# Busboard_v12.net
KiCad netlist of a schematic drawn in EAGLE
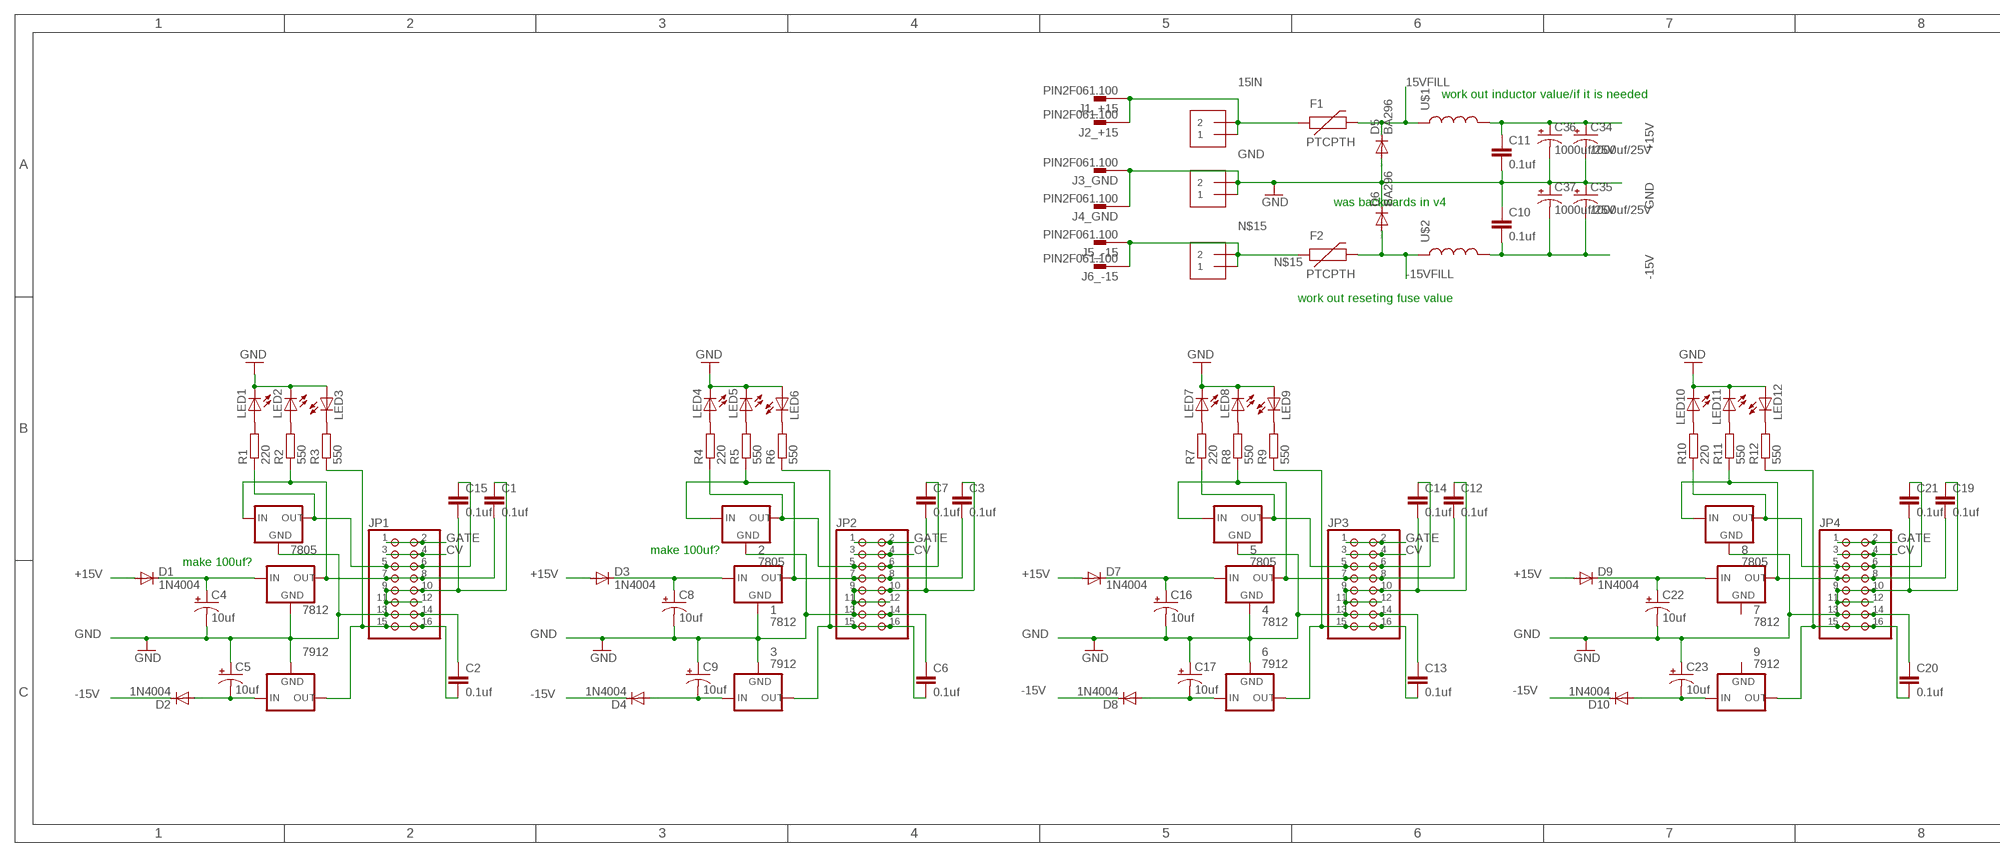
[diagram p0: schematic, sheet 1, part 1 of 2]
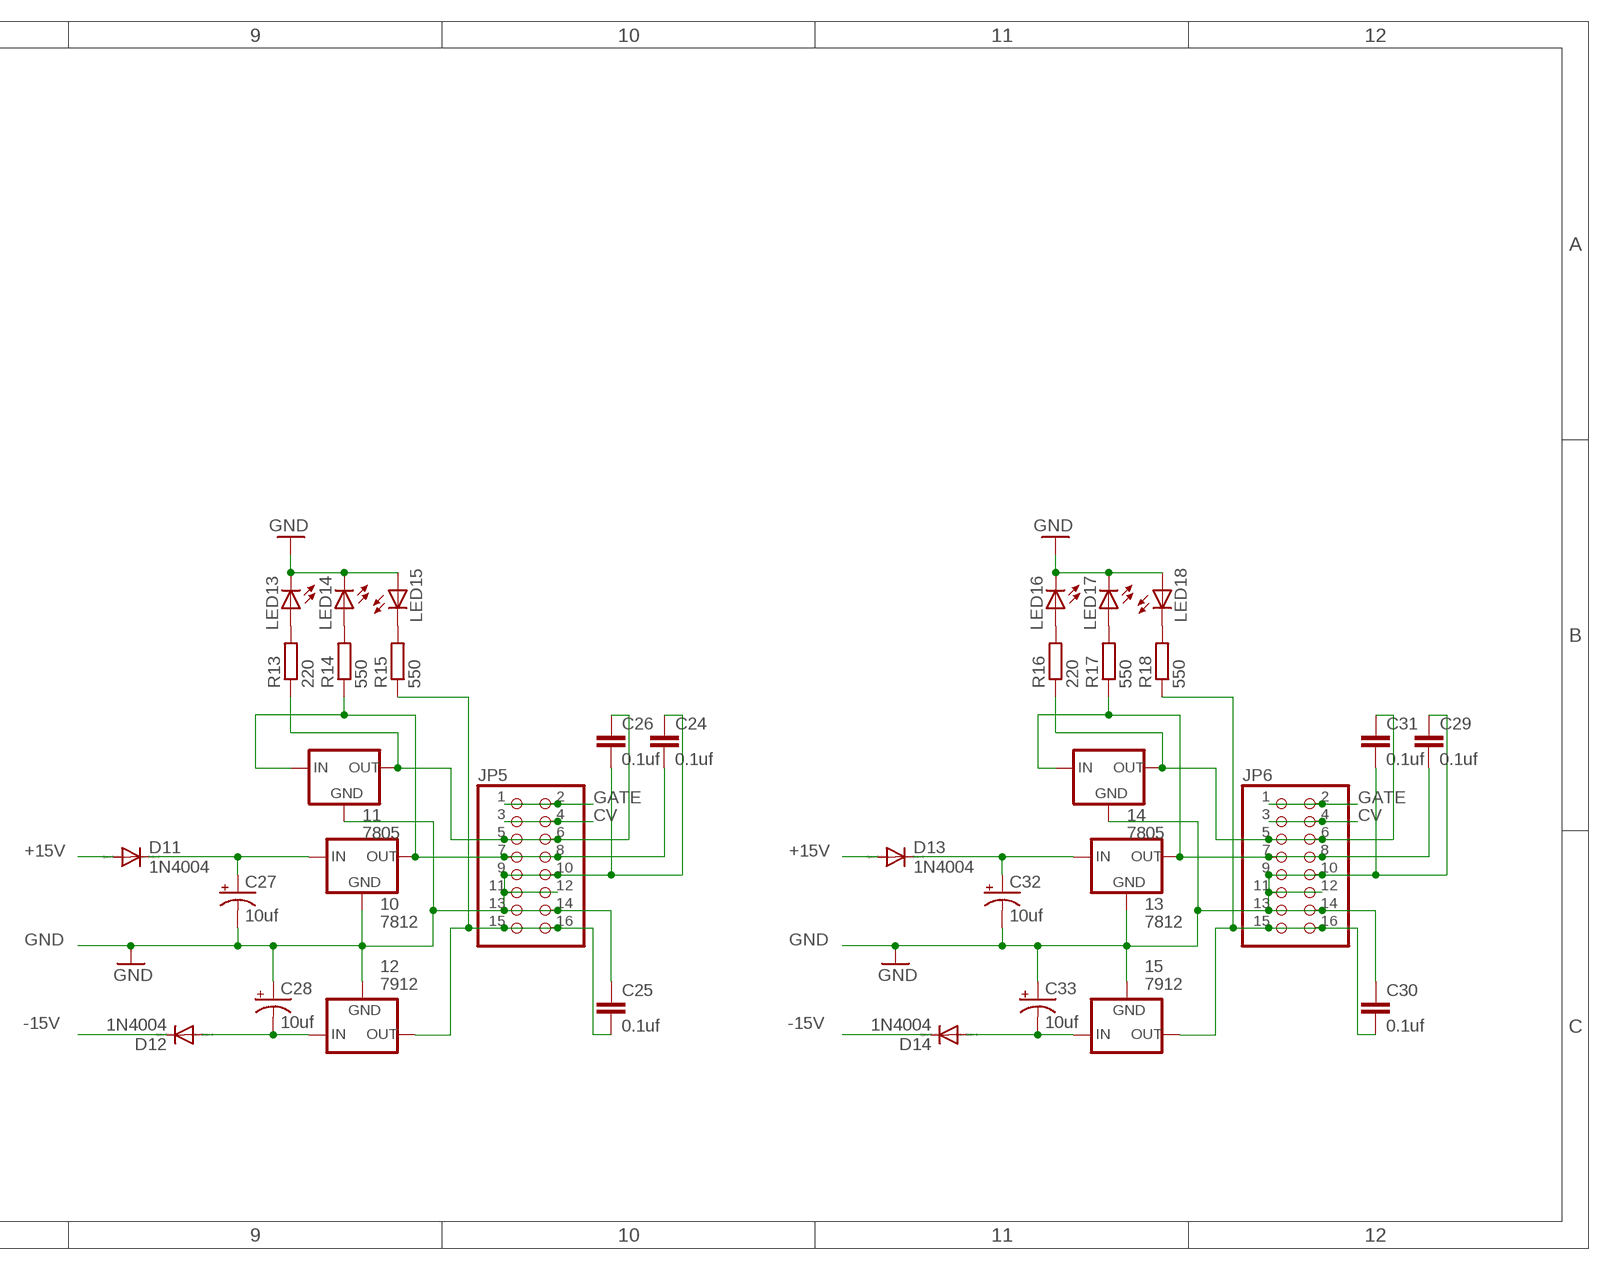
[diagram p1: schematic, sheet 1, part 2 of 2]

(export (version "E")
  (design (tool "Eeschema 10.0.6"))
  (components
    (comp (ref "+15V")
      (value "1X2-3.5MM")
      (footprint "eagle-import:1X2-3.5MM")
      (libsource (lib "eagle-import") (part "1X2-3.5MM"))
    )
    (comp (ref "-15V")
      (value "1X2-3.5MM")
      (footprint "eagle-import:1X2-3.5MM")
      (libsource (lib "eagle-import") (part "1X2-3.5MM"))
    )
    (comp (ref "1")
      (value "7812")
      (footprint "eagle-import:78MXXS")
      (libsource (lib "eagle-import") (part "78MXXS"))
    )
    (comp (ref "2")
      (value "7805")
      (footprint "eagle-import:78MXXS")
      (libsource (lib "eagle-import") (part "78MXXS"))
    )
    (comp (ref "3")
      (value "7912")
      (footprint "eagle-import:79XXS")
      (libsource (lib "eagle-import") (part "79XXS"))
    )
    (comp (ref "4")
      (value "7812")
      (footprint "eagle-import:78MXXS")
      (libsource (lib "eagle-import") (part "78MXXS"))
    )
    (comp (ref "5")
      (value "7805")
      (footprint "eagle-import:78MXXS")
      (libsource (lib "eagle-import") (part "78MXXS"))
    )
    (comp (ref "6")
      (value "7912")
      (footprint "eagle-import:79XXS")
      (libsource (lib "eagle-import") (part "79XXS"))
    )
    (comp (ref "7")
      (value "7812")
      (footprint "eagle-import:78MXXS")
      (libsource (lib "eagle-import") (part "78MXXS"))
    )
    (comp (ref "8")
      (value "7805")
      (footprint "eagle-import:78MXXS")
      (libsource (lib "eagle-import") (part "78MXXS"))
    )
    (comp (ref "9")
      (value "7912")
      (footprint "eagle-import:79XXS")
      (libsource (lib "eagle-import") (part "79XXS"))
    )
    (comp (ref "10")
      (value "7812")
      (footprint "eagle-import:78MXXS")
      (libsource (lib "eagle-import") (part "78MXXS"))
    )
    (comp (ref "11")
      (value "7805")
      (footprint "eagle-import:78MXXS")
      (libsource (lib "eagle-import") (part "78MXXS"))
    )
    (comp (ref "12")
      (value "7912")
      (footprint "eagle-import:79XXS")
      (libsource (lib "eagle-import") (part "79XXS"))
    )
    (comp (ref "13")
      (value "7812")
      (footprint "eagle-import:78MXXS")
      (libsource (lib "eagle-import") (part "78MXXS"))
    )
    (comp (ref "14")
      (value "7805")
      (footprint "eagle-import:78MXXS")
      (libsource (lib "eagle-import") (part "78MXXS"))
    )
    (comp (ref "15")
      (value "7912")
      (footprint "eagle-import:79XXS")
      (libsource (lib "eagle-import") (part "79XXS"))
    )
    (comp (ref "7805")
      (value "78MXXS")
      (footprint "eagle-import:78MXXS")
      (libsource (lib "eagle-import") (part "78MXXS"))
    )
    (comp (ref "7812")
      (value "78MXXS")
      (footprint "eagle-import:78MXXS")
      (libsource (lib "eagle-import") (part "78MXXS"))
    )
    (comp (ref "7912")
      (value "79XXS")
      (footprint "eagle-import:79XXS")
      (libsource (lib "eagle-import") (part "79XXS"))
    )
    (comp (ref "C1")
      (value "0.1uf")
      (footprint "eagle-import:CAP-PTH-SMALL-KIT")
      (libsource (lib "eagle-import") (part "0.1UF-50V-20%(PTH)KIT-EZ"))
    )
    (comp (ref "C2")
      (value "0.1uf")
      (footprint "eagle-import:CAP-PTH-SMALL-KIT")
      (libsource (lib "eagle-import") (part "0.1UF-50V-20%(PTH)KIT-EZ"))
    )
    (comp (ref "C3")
      (value "0.1uf")
      (footprint "eagle-import:CAP-PTH-SMALL-KIT")
      (libsource (lib "eagle-import") (part "0.1UF-50V-20%(PTH)KIT-EZ"))
    )
    (comp (ref "C4")
      (value "10uf")
      (footprint "eagle-import:CPOL-RADIAL-10UF-25V")
      (libsource (lib "eagle-import") (part "10UF-25V-20%(PTH)"))
    )
    (comp (ref "C5")
      (value "10uf")
      (footprint "eagle-import:CPOL-RADIAL-10UF-25V")
      (libsource (lib "eagle-import") (part "10UF-25V-20%(PTH)"))
    )
    (comp (ref "C6")
      (value "0.1uf")
      (footprint "eagle-import:CAP-PTH-SMALL-KIT")
      (libsource (lib "eagle-import") (part "0.1UF-50V-20%(PTH)KIT-EZ"))
    )
    (comp (ref "C7")
      (value "0.1uf")
      (footprint "eagle-import:CAP-PTH-SMALL-KIT")
      (libsource (lib "eagle-import") (part "0.1UF-50V-20%(PTH)KIT-EZ"))
    )
    (comp (ref "C8")
      (value "10uf")
      (footprint "eagle-import:CPOL-RADIAL-10UF-25V")
      (libsource (lib "eagle-import") (part "10UF-25V-20%(PTH)"))
    )
    (comp (ref "C9")
      (value "10uf")
      (footprint "eagle-import:CPOL-RADIAL-10UF-25V")
      (libsource (lib "eagle-import") (part "10UF-25V-20%(PTH)"))
    )
    (comp (ref "C10")
      (value "0.1uf")
      (footprint "eagle-import:CAP-PTH-SMALL-KIT")
      (libsource (lib "eagle-import") (part "0.1UF-50V-20%(PTH)KIT-EZ"))
    )
    (comp (ref "C11")
      (value "0.1uf")
      (footprint "eagle-import:CAP-PTH-SMALL-KIT")
      (libsource (lib "eagle-import") (part "0.1UF-50V-20%(PTH)KIT-EZ"))
    )
    (comp (ref "C12")
      (value "0.1uf")
      (footprint "eagle-import:CAP-PTH-SMALL-KIT")
      (libsource (lib "eagle-import") (part "0.1UF-50V-20%(PTH)KIT-EZ"))
    )
    (comp (ref "C13")
      (value "0.1uf")
      (footprint "eagle-import:CAP-PTH-SMALL-KIT")
      (libsource (lib "eagle-import") (part "0.1UF-50V-20%(PTH)KIT-EZ"))
    )
    (comp (ref "C14")
      (value "0.1uf")
      (footprint "eagle-import:CAP-PTH-SMALL-KIT")
      (libsource (lib "eagle-import") (part "0.1UF-50V-20%(PTH)KIT-EZ"))
    )
    (comp (ref "C15")
      (value "0.1uf")
      (footprint "eagle-import:CAP-PTH-SMALL-KIT")
      (libsource (lib "eagle-import") (part "0.1UF-50V-20%(PTH)KIT-EZ"))
    )
    (comp (ref "C16")
      (value "10uf")
      (footprint "eagle-import:CPOL-RADIAL-10UF-25V")
      (libsource (lib "eagle-import") (part "10UF-25V-20%(PTH)"))
    )
    (comp (ref "C17")
      (value "10uf")
      (footprint "eagle-import:CPOL-RADIAL-10UF-25V")
      (libsource (lib "eagle-import") (part "10UF-25V-20%(PTH)"))
    )
    (comp (ref "C19")
      (value "0.1uf")
      (footprint "eagle-import:CAP-PTH-SMALL-KIT")
      (libsource (lib "eagle-import") (part "0.1UF-50V-20%(PTH)KIT-EZ"))
    )
    (comp (ref "C20")
      (value "0.1uf")
      (footprint "eagle-import:CAP-PTH-SMALL-KIT")
      (libsource (lib "eagle-import") (part "0.1UF-50V-20%(PTH)KIT-EZ"))
    )
    (comp (ref "C21")
      (value "0.1uf")
      (footprint "eagle-import:CAP-PTH-SMALL-KIT")
      (libsource (lib "eagle-import") (part "0.1UF-50V-20%(PTH)KIT-EZ"))
    )
    (comp (ref "C22")
      (value "10uf")
      (footprint "eagle-import:CPOL-RADIAL-10UF-25V")
      (libsource (lib "eagle-import") (part "10UF-25V-20%(PTH)"))
    )
    (comp (ref "C23")
      (value "10uf")
      (footprint "eagle-import:CPOL-RADIAL-10UF-25V")
      (libsource (lib "eagle-import") (part "10UF-25V-20%(PTH)"))
    )
    (comp (ref "C24")
      (value "0.1uf")
      (footprint "eagle-import:CAP-PTH-SMALL-KIT")
      (libsource (lib "eagle-import") (part "0.1UF-50V-20%(PTH)KIT-EZ"))
    )
    (comp (ref "C25")
      (value "0.1uf")
      (footprint "eagle-import:CAP-PTH-SMALL-KIT")
      (libsource (lib "eagle-import") (part "0.1UF-50V-20%(PTH)KIT-EZ"))
    )
    (comp (ref "C26")
      (value "0.1uf")
      (footprint "eagle-import:CAP-PTH-SMALL-KIT")
      (libsource (lib "eagle-import") (part "0.1UF-50V-20%(PTH)KIT-EZ"))
    )
    (comp (ref "C27")
      (value "10uf")
      (footprint "eagle-import:CPOL-RADIAL-10UF-25V")
      (libsource (lib "eagle-import") (part "10UF-25V-20%(PTH)"))
    )
    (comp (ref "C28")
      (value "10uf")
      (footprint "eagle-import:CPOL-RADIAL-10UF-25V")
      (libsource (lib "eagle-import") (part "10UF-25V-20%(PTH)"))
    )
    (comp (ref "C29")
      (value "0.1uf")
      (footprint "eagle-import:CAP-PTH-SMALL-KIT")
      (libsource (lib "eagle-import") (part "0.1UF-50V-20%(PTH)KIT-EZ"))
    )
    (comp (ref "C30")
      (value "0.1uf")
      (footprint "eagle-import:CAP-PTH-SMALL-KIT")
      (libsource (lib "eagle-import") (part "0.1UF-50V-20%(PTH)KIT-EZ"))
    )
    (comp (ref "C31")
      (value "0.1uf")
      (footprint "eagle-import:CAP-PTH-SMALL-KIT")
      (libsource (lib "eagle-import") (part "0.1UF-50V-20%(PTH)KIT-EZ"))
    )
    (comp (ref "C32")
      (value "10uf")
      (footprint "eagle-import:CPOL-RADIAL-10UF-25V")
      (libsource (lib "eagle-import") (part "10UF-25V-20%(PTH)"))
    )
    (comp (ref "C33")
      (value "10uf")
      (footprint "eagle-import:CPOL-RADIAL-10UF-25V")
      (libsource (lib "eagle-import") (part "10UF-25V-20%(PTH)"))
    )
    (comp (ref "C34")
      (value "1000uf/25V")
      (footprint "eagle-import:CPOL-RADIAL-1000UF-25V-KIT")
      (libsource (lib "eagle-import") (part "1000UF-25V(PTH)KIT"))
    )
    (comp (ref "C35")
      (value "1000uf/25V")
      (footprint "eagle-import:CPOL-RADIAL-1000UF-25V-KIT")
      (libsource (lib "eagle-import") (part "1000UF-25V(PTH)KIT"))
    )
    (comp (ref "C36")
      (value "1000uf/25V")
      (footprint "eagle-import:CPOL-RADIAL-1000UF-25V-KIT")
      (libsource (lib "eagle-import") (part "1000UF-25V(PTH)KIT"))
    )
    (comp (ref "C37")
      (value "1000uf/25V")
      (footprint "eagle-import:CPOL-RADIAL-1000UF-25V-KIT")
      (libsource (lib "eagle-import") (part "1000UF-25V(PTH)KIT"))
    )
    (comp (ref "D1")
      (value "1N4004")
      (footprint "eagle-import:DO41-10")
      (libsource (lib "eagle-import") (part "1N4004"))
    )
    (comp (ref "D2")
      (value "1N4004")
      (footprint "eagle-import:DO41-10")
      (libsource (lib "eagle-import") (part "1N4004"))
    )
    (comp (ref "D3")
      (value "1N4004")
      (footprint "eagle-import:DO41-10")
      (libsource (lib "eagle-import") (part "1N4004"))
    )
    (comp (ref "D4")
      (value "1N4004")
      (footprint "eagle-import:DO41-10")
      (libsource (lib "eagle-import") (part "1N4004"))
    )
    (comp (ref "D5")
      (value "BA296")
      (footprint "eagle-import:P2-15")
      (libsource (lib "eagle-import") (part "BA296"))
    )
    (comp (ref "D6")
      (value "BA296")
      (footprint "eagle-import:P2-15")
      (libsource (lib "eagle-import") (part "BA296"))
    )
    (comp (ref "D7")
      (value "1N4004")
      (footprint "eagle-import:DO41-10")
      (libsource (lib "eagle-import") (part "1N4004"))
    )
    (comp (ref "D8")
      (value "1N4004")
      (footprint "eagle-import:DO41-10")
      (libsource (lib "eagle-import") (part "1N4004"))
    )
    (comp (ref "D9")
      (value "1N4004")
      (footprint "eagle-import:DO41-10")
      (libsource (lib "eagle-import") (part "1N4004"))
    )
    (comp (ref "D10")
      (value "1N4004")
      (footprint "eagle-import:DO41-10")
      (libsource (lib "eagle-import") (part "1N4004"))
    )
    (comp (ref "D11")
      (value "1N4004")
      (footprint "eagle-import:DO41-10")
      (libsource (lib "eagle-import") (part "1N4004"))
    )
    (comp (ref "D12")
      (value "1N4004")
      (footprint "eagle-import:DO41-10")
      (libsource (lib "eagle-import") (part "1N4004"))
    )
    (comp (ref "D13")
      (value "1N4004")
      (footprint "eagle-import:DO41-10")
      (libsource (lib "eagle-import") (part "1N4004"))
    )
    (comp (ref "D14")
      (value "1N4004")
      (footprint "eagle-import:DO41-10")
      (libsource (lib "eagle-import") (part "1N4004"))
    )
    (comp (ref "F1")
      (value "PTCPTH")
      (footprint "eagle-import:PTC")
      (libsource (lib "eagle-import") (part "PTCPTH"))
    )
    (comp (ref "F2")
      (value "PTCPTH")
      (footprint "eagle-import:PTC")
      (libsource (lib "eagle-import") (part "PTCPTH"))
    )
    (comp (ref "GND")
      (value "1X2-3.5MM")
      (footprint "eagle-import:1X2-3.5MM")
      (libsource (lib "eagle-import") (part "1X2-3.5MM"))
    )
    (comp (ref "J1_+15")
      (value "PIN2F061.100")
      (footprint "eagle-import:F061.100")
      (libsource (lib "eagle-import") (part "PIN2F061.100"))
    )
    (comp (ref "J2_+15")
      (value "PIN2F061.100")
      (footprint "eagle-import:F061.100")
      (libsource (lib "eagle-import") (part "PIN2F061.100"))
    )
    (comp (ref "J3_GND")
      (value "PIN2F061.100")
      (footprint "eagle-import:F061.100")
      (libsource (lib "eagle-import") (part "PIN2F061.100"))
    )
    (comp (ref "J4_GND")
      (value "PIN2F061.100")
      (footprint "eagle-import:F061.100")
      (libsource (lib "eagle-import") (part "PIN2F061.100"))
    )
    (comp (ref "J5_-15")
      (value "PIN2F061.100")
      (footprint "eagle-import:F061.100")
      (libsource (lib "eagle-import") (part "PIN2F061.100"))
    )
    (comp (ref "J6_-15")
      (value "PIN2F061.100")
      (footprint "eagle-import:F061.100")
      (libsource (lib "eagle-import") (part "PIN2F061.100"))
    )
    (comp (ref "JP1")
      (value "PINHD-2X8")
      (footprint "eagle-import:2X08")
      (libsource (lib "eagle-import") (part "PINHD-2X8"))
    )
    (comp (ref "JP2")
      (value "PINHD-2X8")
      (footprint "eagle-import:2X08")
      (libsource (lib "eagle-import") (part "PINHD-2X8"))
    )
    (comp (ref "JP3")
      (value "PINHD-2X8")
      (footprint "eagle-import:2X08")
      (libsource (lib "eagle-import") (part "PINHD-2X8"))
    )
    (comp (ref "JP4")
      (value "PINHD-2X8")
      (footprint "eagle-import:2X08")
      (libsource (lib "eagle-import") (part "PINHD-2X8"))
    )
    (comp (ref "JP5")
      (value "PINHD-2X8")
      (footprint "eagle-import:2X08")
      (libsource (lib "eagle-import") (part "PINHD-2X8"))
    )
    (comp (ref "JP6")
      (value "PINHD-2X8")
      (footprint "eagle-import:2X08")
      (libsource (lib "eagle-import") (part "PINHD-2X8"))
    )
    (comp (ref "LED1")
      (value "LED3MM")
      (footprint "eagle-import:LED3MM")
      (libsource (lib "eagle-import") (part "LED3MM"))
    )
    (comp (ref "LED2")
      (value "LED3MM")
      (footprint "eagle-import:LED3MM")
      (libsource (lib "eagle-import") (part "LED3MM"))
    )
    (comp (ref "LED3")
      (value "LED3MM")
      (footprint "eagle-import:LED3MM")
      (libsource (lib "eagle-import") (part "LED3MM"))
    )
    (comp (ref "LED4")
      (value "LED3MM")
      (footprint "eagle-import:LED3MM")
      (libsource (lib "eagle-import") (part "LED3MM"))
    )
    (comp (ref "LED5")
      (value "LED3MM")
      (footprint "eagle-import:LED3MM")
      (libsource (lib "eagle-import") (part "LED3MM"))
    )
    (comp (ref "LED6")
      (value "LED3MM")
      (footprint "eagle-import:LED3MM")
      (libsource (lib "eagle-import") (part "LED3MM"))
    )
    (comp (ref "LED7")
      (value "LED3MM")
      (footprint "eagle-import:LED3MM")
      (libsource (lib "eagle-import") (part "LED3MM"))
    )
    (comp (ref "LED8")
      (value "LED3MM")
      (footprint "eagle-import:LED3MM")
      (libsource (lib "eagle-import") (part "LED3MM"))
    )
    (comp (ref "LED9")
      (value "LED3MM")
      (footprint "eagle-import:LED3MM")
      (libsource (lib "eagle-import") (part "LED3MM"))
    )
    (comp (ref "LED10")
      (value "LED3MM")
      (footprint "eagle-import:LED3MM")
      (libsource (lib "eagle-import") (part "LED3MM"))
    )
    (comp (ref "LED11")
      (value "LED3MM")
      (footprint "eagle-import:LED3MM")
      (libsource (lib "eagle-import") (part "LED3MM"))
    )
    (comp (ref "LED12")
      (value "LED3MM")
      (footprint "eagle-import:LED3MM")
      (libsource (lib "eagle-import") (part "LED3MM"))
    )
    (comp (ref "LED13")
      (value "LED3MM")
      (footprint "eagle-import:LED3MM")
      (libsource (lib "eagle-import") (part "LED3MM"))
    )
    (comp (ref "LED14")
      (value "LED3MM")
      (footprint "eagle-import:LED3MM")
      (libsource (lib "eagle-import") (part "LED3MM"))
    )
    (comp (ref "LED15")
      (value "LED3MM")
      (footprint "eagle-import:LED3MM")
      (libsource (lib "eagle-import") (part "LED3MM"))
    )
    (comp (ref "LED16")
      (value "LED3MM")
      (footprint "eagle-import:LED3MM")
      (libsource (lib "eagle-import") (part "LED3MM"))
    )
    (comp (ref "LED17")
      (value "LED3MM")
      (footprint "eagle-import:LED3MM")
      (libsource (lib "eagle-import") (part "LED3MM"))
    )
    (comp (ref "LED18")
      (value "LED3MM")
      (footprint "eagle-import:LED3MM")
      (libsource (lib "eagle-import") (part "LED3MM"))
    )
    (comp (ref "R1")
      (value "220")
      (footprint "eagle-import:0207_5V")
      (libsource (lib "eagle-import") (part "R-EU_0207/5V"))
    )
    (comp (ref "R2")
      (value "550")
      (footprint "eagle-import:0207_5V")
      (libsource (lib "eagle-import") (part "R-EU_0207/5V"))
    )
    (comp (ref "R3")
      (value "550")
      (footprint "eagle-import:0207_5V")
      (libsource (lib "eagle-import") (part "R-EU_0207/5V"))
    )
    (comp (ref "R4")
      (value "220")
      (footprint "eagle-import:0207_5V")
      (libsource (lib "eagle-import") (part "R-EU_0207/5V"))
    )
    (comp (ref "R5")
      (value "550")
      (footprint "eagle-import:0207_5V")
      (libsource (lib "eagle-import") (part "R-EU_0207/5V"))
    )
    (comp (ref "R6")
      (value "550")
      (footprint "eagle-import:0207_5V")
      (libsource (lib "eagle-import") (part "R-EU_0207/5V"))
    )
    (comp (ref "R7")
      (value "220")
      (footprint "eagle-import:0207_5V")
      (libsource (lib "eagle-import") (part "R-EU_0207/5V"))
    )
    (comp (ref "R8")
      (value "550")
      (footprint "eagle-import:0207_5V")
      (libsource (lib "eagle-import") (part "R-EU_0207/5V"))
    )
    (comp (ref "R9")
      (value "550")
      (footprint "eagle-import:0207_5V")
      (libsource (lib "eagle-import") (part "R-EU_0207/5V"))
    )
    (comp (ref "R10")
      (value "220")
      (footprint "eagle-import:0207_5V")
      (libsource (lib "eagle-import") (part "R-EU_0207/5V"))
    )
    (comp (ref "R11")
      (value "550")
      (footprint "eagle-import:0207_5V")
      (libsource (lib "eagle-import") (part "R-EU_0207/5V"))
    )
    (comp (ref "R12")
      (value "550")
      (footprint "eagle-import:0207_5V")
      (libsource (lib "eagle-import") (part "R-EU_0207/5V"))
    )
    (comp (ref "R13")
      (value "220")
      (footprint "eagle-import:0207_5V")
      (libsource (lib "eagle-import") (part "R-EU_0207/5V"))
    )
    (comp (ref "R14")
      (value "550")
      (footprint "eagle-import:0207_5V")
      (libsource (lib "eagle-import") (part "R-EU_0207/5V"))
    )
    (comp (ref "R15")
      (value "550")
      (footprint "eagle-import:0207_5V")
      (libsource (lib "eagle-import") (part "R-EU_0207/5V"))
    )
    (comp (ref "R16")
      (value "220")
      (footprint "eagle-import:0207_5V")
      (libsource (lib "eagle-import") (part "R-EU_0207/5V"))
    )
    (comp (ref "R17")
      (value "550")
      (footprint "eagle-import:0207_5V")
      (libsource (lib "eagle-import") (part "R-EU_0207/5V"))
    )
    (comp (ref "R18")
      (value "550")
      (footprint "eagle-import:0207_5V")
      (libsource (lib "eagle-import") (part "R-EU_0207/5V"))
    )
    (comp (ref "U$1")
      (value "INDUCTORRLB0912")
      (footprint "eagle-import:RLB0912")
      (libsource (lib "eagle-import") (part "INDUCTORRLB0912"))
    )
    (comp (ref "U$2")
      (value "INDUCTORRLB0912")
      (footprint "eagle-import:RLB0912")
      (libsource (lib "eagle-import") (part "INDUCTORRLB0912"))
    )
  )
  (nets
    (net (code "1") (name "/+15V") (class "Default")
      (node (ref "C11") (pin "1") (pinfunction "1_1") (pintype "passive"))
      (node (ref "C34") (pin "+") (pinfunction "+_+") (pintype "passive"))
      (node (ref "C36") (pin "+") (pinfunction "+_+") (pintype "passive"))
      (node (ref "D1") (pin "A") (pinfunction "A_A") (pintype "passive"))
      (node (ref "D11") (pin "A") (pinfunction "A_A") (pintype "passive"))
      (node (ref "D13") (pin "A") (pinfunction "A_A") (pintype "passive"))
      (node (ref "D3") (pin "A") (pinfunction "A_A") (pintype "passive"))
      (node (ref "D7") (pin "A") (pinfunction "A_A") (pintype "passive"))
      (node (ref "D9") (pin "A") (pinfunction "A_A") (pintype "passive"))
      (node (ref "U$1") (pin "2") (pinfunction "2_2") (pintype "passive"))
    )
    (net (code "2") (name "/-15V") (class "Default")
      (node (ref "C10") (pin "2") (pinfunction "2_2") (pintype "passive"))
      (node (ref "C35") (pin "-") (pinfunction "-_-") (pintype "passive"))
      (node (ref "C37") (pin "-") (pinfunction "-_-") (pintype "passive"))
      (node (ref "D10") (pin "C") (pinfunction "C_C") (pintype "passive"))
      (node (ref "D12") (pin "C") (pinfunction "C_C") (pintype "passive"))
      (node (ref "D14") (pin "C") (pinfunction "C_C") (pintype "passive"))
      (node (ref "D2") (pin "C") (pinfunction "C_C") (pintype "passive"))
      (node (ref "D4") (pin "C") (pinfunction "C_C") (pintype "passive"))
      (node (ref "D8") (pin "C") (pinfunction "C_C") (pintype "passive"))
      (node (ref "U$2") (pin "2") (pinfunction "2_2") (pintype "passive"))
    )
    (net (code "3") (name "/-15VFILL") (class "Default")
      (node (ref "D6") (pin "A") (pinfunction "A_A") (pintype "passive"))
      (node (ref "F2") (pin "P$2") (pinfunction "2_P$2") (pintype "bidirectional"))
      (node (ref "U$2") (pin "1") (pinfunction "1_1") (pintype "passive"))
    )
    (net (code "4") (name "/15IN") (class "Default")
      (node (ref "+15V") (pin "1") (pinfunction "1_1") (pintype "passive"))
      (node (ref "+15V") (pin "2") (pinfunction "2_2") (pintype "passive"))
      (node (ref "F1") (pin "P$1") (pinfunction "1_P$1") (pintype "bidirectional"))
      (node (ref "J1_+15") (pin "A1") (pinfunction "1_A1") (pintype "passive"))
      (node (ref "J1_+15") (pin "A2") (pinfunction "1_A2") (pintype "passive"))
      (node (ref "J2_+15") (pin "A1") (pinfunction "1_A1") (pintype "passive"))
      (node (ref "J2_+15") (pin "A2") (pinfunction "1_A2") (pintype "passive"))
    )
    (net (code "5") (name "/15VFILL") (class "Default")
      (node (ref "D5") (pin "C") (pinfunction "C_C") (pintype "passive"))
      (node (ref "F1") (pin "P$2") (pinfunction "2_P$2") (pintype "bidirectional"))
      (node (ref "U$1") (pin "1") (pinfunction "1_1") (pintype "passive"))
    )
    (net (code "6") (name "/CV") (class "Default")
      (node (ref "JP1") (pin "3") (pinfunction "3_3") (pintype "passive"))
      (node (ref "JP1") (pin "4") (pinfunction "4_4") (pintype "passive"))
      (node (ref "JP2") (pin "3") (pinfunction "3_3") (pintype "passive"))
      (node (ref "JP2") (pin "4") (pinfunction "4_4") (pintype "passive"))
      (node (ref "JP3") (pin "3") (pinfunction "3_3") (pintype "passive"))
      (node (ref "JP3") (pin "4") (pinfunction "4_4") (pintype "passive"))
      (node (ref "JP4") (pin "3") (pinfunction "3_3") (pintype "passive"))
      (node (ref "JP4") (pin "4") (pinfunction "4_4") (pintype "passive"))
      (node (ref "JP5") (pin "3") (pinfunction "3_3") (pintype "passive"))
      (node (ref "JP5") (pin "4") (pinfunction "4_4") (pintype "passive"))
      (node (ref "JP6") (pin "3") (pinfunction "3_3") (pintype "passive"))
      (node (ref "JP6") (pin "4") (pinfunction "4_4") (pintype "passive"))
    )
    (net (code "7") (name "/GATE") (class "Default")
      (node (ref "JP1") (pin "1") (pinfunction "1_1") (pintype "passive"))
      (node (ref "JP1") (pin "2") (pinfunction "2_2") (pintype "passive"))
      (node (ref "JP2") (pin "1") (pinfunction "1_1") (pintype "passive"))
      (node (ref "JP2") (pin "2") (pinfunction "2_2") (pintype "passive"))
      (node (ref "JP3") (pin "1") (pinfunction "1_1") (pintype "passive"))
      (node (ref "JP3") (pin "2") (pinfunction "2_2") (pintype "passive"))
      (node (ref "JP4") (pin "1") (pinfunction "1_1") (pintype "passive"))
      (node (ref "JP4") (pin "2") (pinfunction "2_2") (pintype "passive"))
      (node (ref "JP5") (pin "1") (pinfunction "1_1") (pintype "passive"))
      (node (ref "JP5") (pin "2") (pinfunction "2_2") (pintype "passive"))
      (node (ref "JP6") (pin "1") (pinfunction "1_1") (pintype "passive"))
      (node (ref "JP6") (pin "2") (pinfunction "2_2") (pintype "passive"))
    )
    (net (code "8") (name "/N$15") (class "Default")
      (node (ref "-15V") (pin "1") (pinfunction "1_1") (pintype "passive"))
      (node (ref "-15V") (pin "2") (pinfunction "2_2") (pintype "passive"))
      (node (ref "F2") (pin "P$1") (pinfunction "1_P$1") (pintype "bidirectional"))
      (node (ref "J5_-15") (pin "A1") (pinfunction "1_A1") (pintype "passive"))
      (node (ref "J5_-15") (pin "A2") (pinfunction "1_A2") (pintype "passive"))
      (node (ref "J6_-15") (pin "A1") (pinfunction "1_A1") (pintype "passive"))
      (node (ref "J6_-15") (pin "A2") (pinfunction "1_A2") (pintype "passive"))
    )
    (net (code "9") (name "GND") (class "Default")
      (node (ref "1") (pin "GND") (pinfunction "GND_GND") (pintype "input"))
      (node (ref "10") (pin "GND") (pinfunction "GND_GND") (pintype "input"))
      (node (ref "11") (pin "GND") (pinfunction "GND_GND") (pintype "input"))
      (node (ref "12") (pin "GND") (pinfunction "GND_GND") (pintype "input"))
      (node (ref "13") (pin "GND") (pinfunction "GND_GND") (pintype "input"))
      (node (ref "14") (pin "GND") (pinfunction "GND_GND") (pintype "input"))
      (node (ref "15") (pin "GND") (pinfunction "GND_GND") (pintype "input"))
      (node (ref "2") (pin "GND") (pinfunction "GND_GND") (pintype "input"))
      (node (ref "3") (pin "GND") (pinfunction "GND_GND") (pintype "input"))
      (node (ref "4") (pin "GND") (pinfunction "GND_GND") (pintype "input"))
      (node (ref "5") (pin "GND") (pinfunction "GND_GND") (pintype "input"))
      (node (ref "6") (pin "GND") (pinfunction "GND_GND") (pintype "input"))
      (node (ref "7805") (pin "GND") (pinfunction "GND_GND") (pintype "input"))
      (node (ref "7812") (pin "GND") (pinfunction "GND_GND") (pintype "input"))
      (node (ref "7912") (pin "GND") (pinfunction "GND_GND") (pintype "input"))
      (node (ref "8") (pin "GND") (pinfunction "GND_GND") (pintype "input"))
      (node (ref "C1") (pin "1") (pinfunction "1_1") (pintype "passive"))
      (node (ref "C10") (pin "1") (pinfunction "1_1") (pintype "passive"))
      (node (ref "C11") (pin "2") (pinfunction "2_2") (pintype "passive"))
      (node (ref "C12") (pin "1") (pinfunction "1_1") (pintype "passive"))
      (node (ref "C13") (pin "1") (pinfunction "1_1") (pintype "passive"))
      (node (ref "C14") (pin "2") (pinfunction "2_2") (pintype "passive"))
      (node (ref "C15") (pin "2") (pinfunction "2_2") (pintype "passive"))
      (node (ref "C16") (pin "2") (pinfunction "-_2") (pintype "passive"))
      (node (ref "C17") (pin "1") (pinfunction "+_1") (pintype "passive"))
      (node (ref "C19") (pin "1") (pinfunction "1_1") (pintype "passive"))
      (node (ref "C2") (pin "1") (pinfunction "1_1") (pintype "passive"))
      (node (ref "C20") (pin "1") (pinfunction "1_1") (pintype "passive"))
      (node (ref "C21") (pin "2") (pinfunction "2_2") (pintype "passive"))
      (node (ref "C22") (pin "2") (pinfunction "-_2") (pintype "passive"))
      (node (ref "C23") (pin "1") (pinfunction "+_1") (pintype "passive"))
      (node (ref "C24") (pin "1") (pinfunction "1_1") (pintype "passive"))
      (node (ref "C25") (pin "1") (pinfunction "1_1") (pintype "passive"))
      (node (ref "C26") (pin "2") (pinfunction "2_2") (pintype "passive"))
      (node (ref "C27") (pin "2") (pinfunction "-_2") (pintype "passive"))
      (node (ref "C28") (pin "1") (pinfunction "+_1") (pintype "passive"))
      (node (ref "C29") (pin "1") (pinfunction "1_1") (pintype "passive"))
      (node (ref "C3") (pin "1") (pinfunction "1_1") (pintype "passive"))
      (node (ref "C30") (pin "1") (pinfunction "1_1") (pintype "passive"))
      (node (ref "C31") (pin "2") (pinfunction "2_2") (pintype "passive"))
      (node (ref "C32") (pin "2") (pinfunction "-_2") (pintype "passive"))
      (node (ref "C33") (pin "1") (pinfunction "+_1") (pintype "passive"))
      (node (ref "C34") (pin "-") (pinfunction "-_-") (pintype "passive"))
      (node (ref "C35") (pin "+") (pinfunction "+_+") (pintype "passive"))
      (node (ref "C36") (pin "-") (pinfunction "-_-") (pintype "passive"))
      (node (ref "C37") (pin "+") (pinfunction "+_+") (pintype "passive"))
      (node (ref "C4") (pin "2") (pinfunction "-_2") (pintype "passive"))
      (node (ref "C5") (pin "1") (pinfunction "+_1") (pintype "passive"))
      (node (ref "C6") (pin "1") (pinfunction "1_1") (pintype "passive"))
      (node (ref "C7") (pin "2") (pinfunction "2_2") (pintype "passive"))
      (node (ref "C8") (pin "2") (pinfunction "-_2") (pintype "passive"))
      (node (ref "C9") (pin "1") (pinfunction "+_1") (pintype "passive"))
      (node (ref "D5") (pin "A") (pinfunction "A_A") (pintype "passive"))
      (node (ref "D6") (pin "C") (pinfunction "C_C") (pintype "passive"))
      (node (ref "GND") (pin "1") (pinfunction "1_1") (pintype "passive"))
      (node (ref "GND") (pin "2") (pinfunction "2_2") (pintype "passive"))
      (node (ref "J3_GND") (pin "A1") (pinfunction "1_A1") (pintype "passive"))
      (node (ref "J3_GND") (pin "A2") (pinfunction "1_A2") (pintype "passive"))
      (node (ref "J4_GND") (pin "A1") (pinfunction "1_A1") (pintype "passive"))
      (node (ref "J4_GND") (pin "A2") (pinfunction "1_A2") (pintype "passive"))
      (node (ref "JP1") (pin "10") (pinfunction "10_10") (pintype "passive"))
      (node (ref "JP1") (pin "11") (pinfunction "11_11") (pintype "passive"))
      (node (ref "JP1") (pin "12") (pinfunction "12_12") (pintype "passive"))
      (node (ref "JP1") (pin "13") (pinfunction "13_13") (pintype "passive"))
      (node (ref "JP1") (pin "14") (pinfunction "14_14") (pintype "passive"))
      (node (ref "JP1") (pin "9") (pinfunction "9_9") (pintype "passive"))
      (node (ref "JP2") (pin "10") (pinfunction "10_10") (pintype "passive"))
      (node (ref "JP2") (pin "11") (pinfunction "11_11") (pintype "passive"))
      (node (ref "JP2") (pin "12") (pinfunction "12_12") (pintype "passive"))
      (node (ref "JP2") (pin "13") (pinfunction "13_13") (pintype "passive"))
      (node (ref "JP2") (pin "14") (pinfunction "14_14") (pintype "passive"))
      (node (ref "JP2") (pin "9") (pinfunction "9_9") (pintype "passive"))
      (node (ref "JP3") (pin "10") (pinfunction "10_10") (pintype "passive"))
      (node (ref "JP3") (pin "11") (pinfunction "11_11") (pintype "passive"))
      (node (ref "JP3") (pin "12") (pinfunction "12_12") (pintype "passive"))
      (node (ref "JP3") (pin "13") (pinfunction "13_13") (pintype "passive"))
      (node (ref "JP3") (pin "14") (pinfunction "14_14") (pintype "passive"))
      (node (ref "JP3") (pin "9") (pinfunction "9_9") (pintype "passive"))
      (node (ref "JP4") (pin "10") (pinfunction "10_10") (pintype "passive"))
      (node (ref "JP4") (pin "11") (pinfunction "11_11") (pintype "passive"))
      (node (ref "JP4") (pin "12") (pinfunction "12_12") (pintype "passive"))
      (node (ref "JP4") (pin "13") (pinfunction "13_13") (pintype "passive"))
      (node (ref "JP4") (pin "14") (pinfunction "14_14") (pintype "passive"))
      (node (ref "JP4") (pin "9") (pinfunction "9_9") (pintype "passive"))
      (node (ref "JP5") (pin "10") (pinfunction "10_10") (pintype "passive"))
      (node (ref "JP5") (pin "11") (pinfunction "11_11") (pintype "passive"))
      (node (ref "JP5") (pin "12") (pinfunction "12_12") (pintype "passive"))
      (node (ref "JP5") (pin "13") (pinfunction "13_13") (pintype "passive"))
      (node (ref "JP5") (pin "14") (pinfunction "14_14") (pintype "passive"))
      (node (ref "JP5") (pin "9") (pinfunction "9_9") (pintype "passive"))
      (node (ref "JP6") (pin "10") (pinfunction "10_10") (pintype "passive"))
      (node (ref "JP6") (pin "11") (pinfunction "11_11") (pintype "passive"))
      (node (ref "JP6") (pin "12") (pinfunction "12_12") (pintype "passive"))
      (node (ref "JP6") (pin "13") (pinfunction "13_13") (pintype "passive"))
      (node (ref "JP6") (pin "14") (pinfunction "14_14") (pintype "passive"))
      (node (ref "JP6") (pin "9") (pinfunction "9_9") (pintype "passive"))
      (node (ref "LED1") (pin "K") (pinfunction "C_K") (pintype "passive"))
      (node (ref "LED10") (pin "K") (pinfunction "C_K") (pintype "passive"))
      (node (ref "LED11") (pin "K") (pinfunction "C_K") (pintype "passive"))
      (node (ref "LED12") (pin "A") (pinfunction "A_A") (pintype "passive"))
      (node (ref "LED13") (pin "K") (pinfunction "C_K") (pintype "passive"))
      (node (ref "LED14") (pin "K") (pinfunction "C_K") (pintype "passive"))
      (node (ref "LED15") (pin "A") (pinfunction "A_A") (pintype "passive"))
      (node (ref "LED16") (pin "K") (pinfunction "C_K") (pintype "passive"))
      (node (ref "LED17") (pin "K") (pinfunction "C_K") (pintype "passive"))
      (node (ref "LED18") (pin "A") (pinfunction "A_A") (pintype "passive"))
      (node (ref "LED2") (pin "K") (pinfunction "C_K") (pintype "passive"))
      (node (ref "LED3") (pin "A") (pinfunction "A_A") (pintype "passive"))
      (node (ref "LED4") (pin "K") (pinfunction "C_K") (pintype "passive"))
      (node (ref "LED5") (pin "K") (pinfunction "C_K") (pintype "passive"))
      (node (ref "LED6") (pin "A") (pinfunction "A_A") (pintype "passive"))
      (node (ref "LED7") (pin "K") (pinfunction "C_K") (pintype "passive"))
      (node (ref "LED8") (pin "K") (pinfunction "C_K") (pintype "passive"))
      (node (ref "LED9") (pin "A") (pinfunction "A_A") (pintype "passive"))
    )
    (net (code "10") (name "Net-(1-PadOUT)") (class "Default")
      (node (ref "1") (pin "OUT") (pinfunction "OUT_OUT") (pintype "passive"))
      (node (ref "2") (pin "IN") (pinfunction "IN_IN") (pintype "input"))
      (node (ref "C3") (pin "2") (pinfunction "2_2") (pintype "passive"))
      (node (ref "JP2") (pin "7") (pinfunction "7_7") (pintype "passive"))
      (node (ref "JP2") (pin "8") (pinfunction "8_8") (pintype "passive"))
      (node (ref "R5") (pin "1") (pinfunction "1_1") (pintype "passive"))
    )
    (net (code "11") (name "Net-(2-PadOUT)") (class "Default")
      (node (ref "2") (pin "OUT") (pinfunction "OUT_OUT") (pintype "passive"))
      (node (ref "C7") (pin "1") (pinfunction "1_1") (pintype "passive"))
      (node (ref "JP2") (pin "5") (pinfunction "5_5") (pintype "passive"))
      (node (ref "JP2") (pin "6") (pinfunction "6_6") (pintype "passive"))
      (node (ref "R4") (pin "1") (pinfunction "1_1") (pintype "passive"))
    )
    (net (code "12") (name "Net-(3-PadOUT)") (class "Default")
      (node (ref "3") (pin "OUT") (pinfunction "OUT_OUT") (pintype "passive"))
      (node (ref "C6") (pin "2") (pinfunction "2_2") (pintype "passive"))
      (node (ref "JP2") (pin "15") (pinfunction "15_15") (pintype "passive"))
      (node (ref "JP2") (pin "16") (pinfunction "16_16") (pintype "passive"))
      (node (ref "R6") (pin "1") (pinfunction "1_1") (pintype "passive"))
    )
    (net (code "13") (name "Net-(4-PadOUT)") (class "Default")
      (node (ref "4") (pin "OUT") (pinfunction "OUT_OUT") (pintype "passive"))
      (node (ref "5") (pin "IN") (pinfunction "IN_IN") (pintype "input"))
      (node (ref "C12") (pin "2") (pinfunction "2_2") (pintype "passive"))
      (node (ref "JP3") (pin "7") (pinfunction "7_7") (pintype "passive"))
      (node (ref "JP3") (pin "8") (pinfunction "8_8") (pintype "passive"))
      (node (ref "R8") (pin "1") (pinfunction "1_1") (pintype "passive"))
    )
    (net (code "14") (name "Net-(5-PadOUT)") (class "Default")
      (node (ref "5") (pin "OUT") (pinfunction "OUT_OUT") (pintype "passive"))
      (node (ref "C14") (pin "1") (pinfunction "1_1") (pintype "passive"))
      (node (ref "JP3") (pin "5") (pinfunction "5_5") (pintype "passive"))
      (node (ref "JP3") (pin "6") (pinfunction "6_6") (pintype "passive"))
      (node (ref "R7") (pin "1") (pinfunction "1_1") (pintype "passive"))
    )
    (net (code "15") (name "Net-(6-PadOUT)") (class "Default")
      (node (ref "6") (pin "OUT") (pinfunction "OUT_OUT") (pintype "passive"))
      (node (ref "C13") (pin "2") (pinfunction "2_2") (pintype "passive"))
      (node (ref "JP3") (pin "15") (pinfunction "15_15") (pintype "passive"))
      (node (ref "JP3") (pin "16") (pinfunction "16_16") (pintype "passive"))
      (node (ref "R9") (pin "1") (pinfunction "1_1") (pintype "passive"))
    )
    (net (code "16") (name "Net-(7-PadOUT)") (class "Default")
      (node (ref "7") (pin "OUT") (pinfunction "OUT_OUT") (pintype "passive"))
      (node (ref "8") (pin "IN") (pinfunction "IN_IN") (pintype "input"))
      (node (ref "C19") (pin "2") (pinfunction "2_2") (pintype "passive"))
      (node (ref "JP4") (pin "7") (pinfunction "7_7") (pintype "passive"))
      (node (ref "JP4") (pin "8") (pinfunction "8_8") (pintype "passive"))
      (node (ref "R11") (pin "1") (pinfunction "1_1") (pintype "passive"))
    )
    (net (code "17") (name "Net-(8-PadOUT)") (class "Default")
      (node (ref "8") (pin "OUT") (pinfunction "OUT_OUT") (pintype "passive"))
      (node (ref "C21") (pin "1") (pinfunction "1_1") (pintype "passive"))
      (node (ref "JP4") (pin "5") (pinfunction "5_5") (pintype "passive"))
      (node (ref "JP4") (pin "6") (pinfunction "6_6") (pintype "passive"))
      (node (ref "R10") (pin "1") (pinfunction "1_1") (pintype "passive"))
    )
    (net (code "18") (name "Net-(9-PadOUT)") (class "Default")
      (node (ref "9") (pin "OUT") (pinfunction "OUT_OUT") (pintype "passive"))
      (node (ref "C20") (pin "2") (pinfunction "2_2") (pintype "passive"))
      (node (ref "JP4") (pin "15") (pinfunction "15_15") (pintype "passive"))
      (node (ref "JP4") (pin "16") (pinfunction "16_16") (pintype "passive"))
      (node (ref "R12") (pin "1") (pinfunction "1_1") (pintype "passive"))
    )
    (net (code "19") (name "Net-(10-PadOUT)") (class "Default")
      (node (ref "10") (pin "OUT") (pinfunction "OUT_OUT") (pintype "passive"))
      (node (ref "11") (pin "IN") (pinfunction "IN_IN") (pintype "input"))
      (node (ref "C24") (pin "2") (pinfunction "2_2") (pintype "passive"))
      (node (ref "JP5") (pin "7") (pinfunction "7_7") (pintype "passive"))
      (node (ref "JP5") (pin "8") (pinfunction "8_8") (pintype "passive"))
      (node (ref "R14") (pin "1") (pinfunction "1_1") (pintype "passive"))
    )
    (net (code "20") (name "Net-(11-PadOUT)") (class "Default")
      (node (ref "11") (pin "OUT") (pinfunction "OUT_OUT") (pintype "passive"))
      (node (ref "C26") (pin "1") (pinfunction "1_1") (pintype "passive"))
      (node (ref "JP5") (pin "5") (pinfunction "5_5") (pintype "passive"))
      (node (ref "JP5") (pin "6") (pinfunction "6_6") (pintype "passive"))
      (node (ref "R13") (pin "1") (pinfunction "1_1") (pintype "passive"))
    )
    (net (code "21") (name "Net-(12-PadOUT)") (class "Default")
      (node (ref "12") (pin "OUT") (pinfunction "OUT_OUT") (pintype "passive"))
      (node (ref "C25") (pin "2") (pinfunction "2_2") (pintype "passive"))
      (node (ref "JP5") (pin "15") (pinfunction "15_15") (pintype "passive"))
      (node (ref "JP5") (pin "16") (pinfunction "16_16") (pintype "passive"))
      (node (ref "R15") (pin "1") (pinfunction "1_1") (pintype "passive"))
    )
    (net (code "22") (name "Net-(13-PadOUT)") (class "Default")
      (node (ref "13") (pin "OUT") (pinfunction "OUT_OUT") (pintype "passive"))
      (node (ref "14") (pin "IN") (pinfunction "IN_IN") (pintype "input"))
      (node (ref "C29") (pin "2") (pinfunction "2_2") (pintype "passive"))
      (node (ref "JP6") (pin "7") (pinfunction "7_7") (pintype "passive"))
      (node (ref "JP6") (pin "8") (pinfunction "8_8") (pintype "passive"))
      (node (ref "R17") (pin "1") (pinfunction "1_1") (pintype "passive"))
    )
    (net (code "23") (name "Net-(14-PadOUT)") (class "Default")
      (node (ref "14") (pin "OUT") (pinfunction "OUT_OUT") (pintype "passive"))
      (node (ref "C31") (pin "1") (pinfunction "1_1") (pintype "passive"))
      (node (ref "JP6") (pin "5") (pinfunction "5_5") (pintype "passive"))
      (node (ref "JP6") (pin "6") (pinfunction "6_6") (pintype "passive"))
      (node (ref "R16") (pin "1") (pinfunction "1_1") (pintype "passive"))
    )
    (net (code "24") (name "Net-(15-PadOUT)") (class "Default")
      (node (ref "15") (pin "OUT") (pinfunction "OUT_OUT") (pintype "passive"))
      (node (ref "C30") (pin "2") (pinfunction "2_2") (pintype "passive"))
      (node (ref "JP6") (pin "15") (pinfunction "15_15") (pintype "passive"))
      (node (ref "JP6") (pin "16") (pinfunction "16_16") (pintype "passive"))
      (node (ref "R18") (pin "1") (pinfunction "1_1") (pintype "passive"))
    )
    (net (code "25") (name "Net-(7805-PadIN)") (class "Default")
      (node (ref "7805") (pin "IN") (pinfunction "IN_IN") (pintype "input"))
      (node (ref "7812") (pin "OUT") (pinfunction "OUT_OUT") (pintype "passive"))
      (node (ref "C1") (pin "2") (pinfunction "2_2") (pintype "passive"))
      (node (ref "JP1") (pin "7") (pinfunction "7_7") (pintype "passive"))
      (node (ref "JP1") (pin "8") (pinfunction "8_8") (pintype "passive"))
      (node (ref "R2") (pin "1") (pinfunction "1_1") (pintype "passive"))
    )
    (net (code "26") (name "Net-(7805-PadOUT)") (class "Default")
      (node (ref "7805") (pin "OUT") (pinfunction "OUT_OUT") (pintype "passive"))
      (node (ref "C15") (pin "1") (pinfunction "1_1") (pintype "passive"))
      (node (ref "JP1") (pin "5") (pinfunction "5_5") (pintype "passive"))
      (node (ref "JP1") (pin "6") (pinfunction "6_6") (pintype "passive"))
      (node (ref "R1") (pin "1") (pinfunction "1_1") (pintype "passive"))
    )
    (net (code "27") (name "Net-(7912-PadOUT)") (class "Default")
      (node (ref "7912") (pin "OUT") (pinfunction "OUT_OUT") (pintype "passive"))
      (node (ref "C2") (pin "2") (pinfunction "2_2") (pintype "passive"))
      (node (ref "JP1") (pin "15") (pinfunction "15_15") (pintype "passive"))
      (node (ref "JP1") (pin "16") (pinfunction "16_16") (pintype "passive"))
      (node (ref "R3") (pin "1") (pinfunction "1_1") (pintype "passive"))
    )
    (net (code "28") (name "Net-(C4-+)") (class "Default")
      (node (ref "7812") (pin "IN") (pinfunction "IN_IN") (pintype "input"))
      (node (ref "C4") (pin "1") (pinfunction "+_1") (pintype "passive"))
      (node (ref "D1") (pin "C") (pinfunction "C_C") (pintype "passive"))
    )
    (net (code "29") (name "Net-(C5--)") (class "Default")
      (node (ref "7912") (pin "IN") (pinfunction "IN_IN") (pintype "input"))
      (node (ref "C5") (pin "2") (pinfunction "-_2") (pintype "passive"))
      (node (ref "D2") (pin "A") (pinfunction "A_A") (pintype "passive"))
    )
    (net (code "30") (name "Net-(C8-+)") (class "Default")
      (node (ref "1") (pin "IN") (pinfunction "IN_IN") (pintype "input"))
      (node (ref "C8") (pin "1") (pinfunction "+_1") (pintype "passive"))
      (node (ref "D3") (pin "C") (pinfunction "C_C") (pintype "passive"))
    )
    (net (code "31") (name "Net-(C9--)") (class "Default")
      (node (ref "3") (pin "IN") (pinfunction "IN_IN") (pintype "input"))
      (node (ref "C9") (pin "2") (pinfunction "-_2") (pintype "passive"))
      (node (ref "D4") (pin "A") (pinfunction "A_A") (pintype "passive"))
    )
    (net (code "32") (name "Net-(C16-+)") (class "Default")
      (node (ref "4") (pin "IN") (pinfunction "IN_IN") (pintype "input"))
      (node (ref "C16") (pin "1") (pinfunction "+_1") (pintype "passive"))
      (node (ref "D7") (pin "C") (pinfunction "C_C") (pintype "passive"))
    )
    (net (code "33") (name "Net-(C17--)") (class "Default")
      (node (ref "6") (pin "IN") (pinfunction "IN_IN") (pintype "input"))
      (node (ref "C17") (pin "2") (pinfunction "-_2") (pintype "passive"))
      (node (ref "D8") (pin "A") (pinfunction "A_A") (pintype "passive"))
    )
    (net (code "34") (name "Net-(C22-+)") (class "Default")
      (node (ref "7") (pin "IN") (pinfunction "IN_IN") (pintype "input"))
      (node (ref "C22") (pin "1") (pinfunction "+_1") (pintype "passive"))
      (node (ref "D9") (pin "C") (pinfunction "C_C") (pintype "passive"))
    )
    (net (code "35") (name "Net-(C23--)") (class "Default")
      (node (ref "9") (pin "IN") (pinfunction "IN_IN") (pintype "input"))
      (node (ref "C23") (pin "2") (pinfunction "-_2") (pintype "passive"))
      (node (ref "D10") (pin "A") (pinfunction "A_A") (pintype "passive"))
    )
    (net (code "36") (name "Net-(C27-+)") (class "Default")
      (node (ref "10") (pin "IN") (pinfunction "IN_IN") (pintype "input"))
      (node (ref "C27") (pin "1") (pinfunction "+_1") (pintype "passive"))
      (node (ref "D11") (pin "C") (pinfunction "C_C") (pintype "passive"))
    )
    (net (code "37") (name "Net-(C28--)") (class "Default")
      (node (ref "12") (pin "IN") (pinfunction "IN_IN") (pintype "input"))
      (node (ref "C28") (pin "2") (pinfunction "-_2") (pintype "passive"))
      (node (ref "D12") (pin "A") (pinfunction "A_A") (pintype "passive"))
    )
    (net (code "38") (name "Net-(C32-+)") (class "Default")
      (node (ref "13") (pin "IN") (pinfunction "IN_IN") (pintype "input"))
      (node (ref "C32") (pin "1") (pinfunction "+_1") (pintype "passive"))
      (node (ref "D13") (pin "C") (pinfunction "C_C") (pintype "passive"))
    )
    (net (code "39") (name "Net-(C33--)") (class "Default")
      (node (ref "15") (pin "IN") (pinfunction "IN_IN") (pintype "input"))
      (node (ref "C33") (pin "2") (pinfunction "-_2") (pintype "passive"))
      (node (ref "D14") (pin "A") (pinfunction "A_A") (pintype "passive"))
    )
    (net (code "40") (name "Net-(LED1-PadA)") (class "Default")
      (node (ref "LED1") (pin "A") (pinfunction "A_A") (pintype "passive"))
      (node (ref "R1") (pin "2") (pinfunction "2_2") (pintype "passive"))
    )
    (net (code "41") (name "Net-(LED2-PadA)") (class "Default")
      (node (ref "LED2") (pin "A") (pinfunction "A_A") (pintype "passive"))
      (node (ref "R2") (pin "2") (pinfunction "2_2") (pintype "passive"))
    )
    (net (code "42") (name "Net-(LED3-C)") (class "Default")
      (node (ref "LED3") (pin "K") (pinfunction "C_K") (pintype "passive"))
      (node (ref "R3") (pin "2") (pinfunction "2_2") (pintype "passive"))
    )
    (net (code "43") (name "Net-(LED4-PadA)") (class "Default")
      (node (ref "LED4") (pin "A") (pinfunction "A_A") (pintype "passive"))
      (node (ref "R4") (pin "2") (pinfunction "2_2") (pintype "passive"))
    )
    (net (code "44") (name "Net-(LED5-PadA)") (class "Default")
      (node (ref "LED5") (pin "A") (pinfunction "A_A") (pintype "passive"))
      (node (ref "R5") (pin "2") (pinfunction "2_2") (pintype "passive"))
    )
    (net (code "45") (name "Net-(LED6-C)") (class "Default")
      (node (ref "LED6") (pin "K") (pinfunction "C_K") (pintype "passive"))
      (node (ref "R6") (pin "2") (pinfunction "2_2") (pintype "passive"))
    )
    (net (code "46") (name "Net-(LED7-PadA)") (class "Default")
      (node (ref "LED7") (pin "A") (pinfunction "A_A") (pintype "passive"))
      (node (ref "R7") (pin "2") (pinfunction "2_2") (pintype "passive"))
    )
    (net (code "47") (name "Net-(LED8-PadA)") (class "Default")
      (node (ref "LED8") (pin "A") (pinfunction "A_A") (pintype "passive"))
      (node (ref "R8") (pin "2") (pinfunction "2_2") (pintype "passive"))
    )
    (net (code "48") (name "Net-(LED9-C)") (class "Default")
      (node (ref "LED9") (pin "K") (pinfunction "C_K") (pintype "passive"))
      (node (ref "R9") (pin "2") (pinfunction "2_2") (pintype "passive"))
    )
    (net (code "49") (name "Net-(LED10-PadA)") (class "Default")
      (node (ref "LED10") (pin "A") (pinfunction "A_A") (pintype "passive"))
      (node (ref "R10") (pin "2") (pinfunction "2_2") (pintype "passive"))
    )
    (net (code "50") (name "Net-(LED11-PadA)") (class "Default")
      (node (ref "LED11") (pin "A") (pinfunction "A_A") (pintype "passive"))
      (node (ref "R11") (pin "2") (pinfunction "2_2") (pintype "passive"))
    )
    (net (code "51") (name "Net-(LED12-C)") (class "Default")
      (node (ref "LED12") (pin "K") (pinfunction "C_K") (pintype "passive"))
      (node (ref "R12") (pin "2") (pinfunction "2_2") (pintype "passive"))
    )
    (net (code "52") (name "Net-(LED13-PadA)") (class "Default")
      (node (ref "LED13") (pin "A") (pinfunction "A_A") (pintype "passive"))
      (node (ref "R13") (pin "2") (pinfunction "2_2") (pintype "passive"))
    )
    (net (code "53") (name "Net-(LED14-PadA)") (class "Default")
      (node (ref "LED14") (pin "A") (pinfunction "A_A") (pintype "passive"))
      (node (ref "R14") (pin "2") (pinfunction "2_2") (pintype "passive"))
    )
    (net (code "54") (name "Net-(LED15-C)") (class "Default")
      (node (ref "LED15") (pin "K") (pinfunction "C_K") (pintype "passive"))
      (node (ref "R15") (pin "2") (pinfunction "2_2") (pintype "passive"))
    )
    (net (code "55") (name "Net-(LED16-PadA)") (class "Default")
      (node (ref "LED16") (pin "A") (pinfunction "A_A") (pintype "passive"))
      (node (ref "R16") (pin "2") (pinfunction "2_2") (pintype "passive"))
    )
    (net (code "56") (name "Net-(LED17-PadA)") (class "Default")
      (node (ref "LED17") (pin "A") (pinfunction "A_A") (pintype "passive"))
      (node (ref "R17") (pin "2") (pinfunction "2_2") (pintype "passive"))
    )
    (net (code "57") (name "Net-(LED18-C)") (class "Default")
      (node (ref "LED18") (pin "K") (pinfunction "C_K") (pintype "passive"))
      (node (ref "R18") (pin "2") (pinfunction "2_2") (pintype "passive"))
    )
    (net (code "58") (name "unconnected-(7-PadGND)") (class "Default")
      (node (ref "7") (pin "GND") (pinfunction "GND_GND") (pintype "input"))
    )
    (net (code "59") (name "unconnected-(9-PadGND)") (class "Default")
      (node (ref "9") (pin "GND") (pinfunction "GND_GND") (pintype "input"))
    )
  )
)
